# dynalo_SMD_MOD.net
KiCad netlist of a schematic drawn in EAGLE
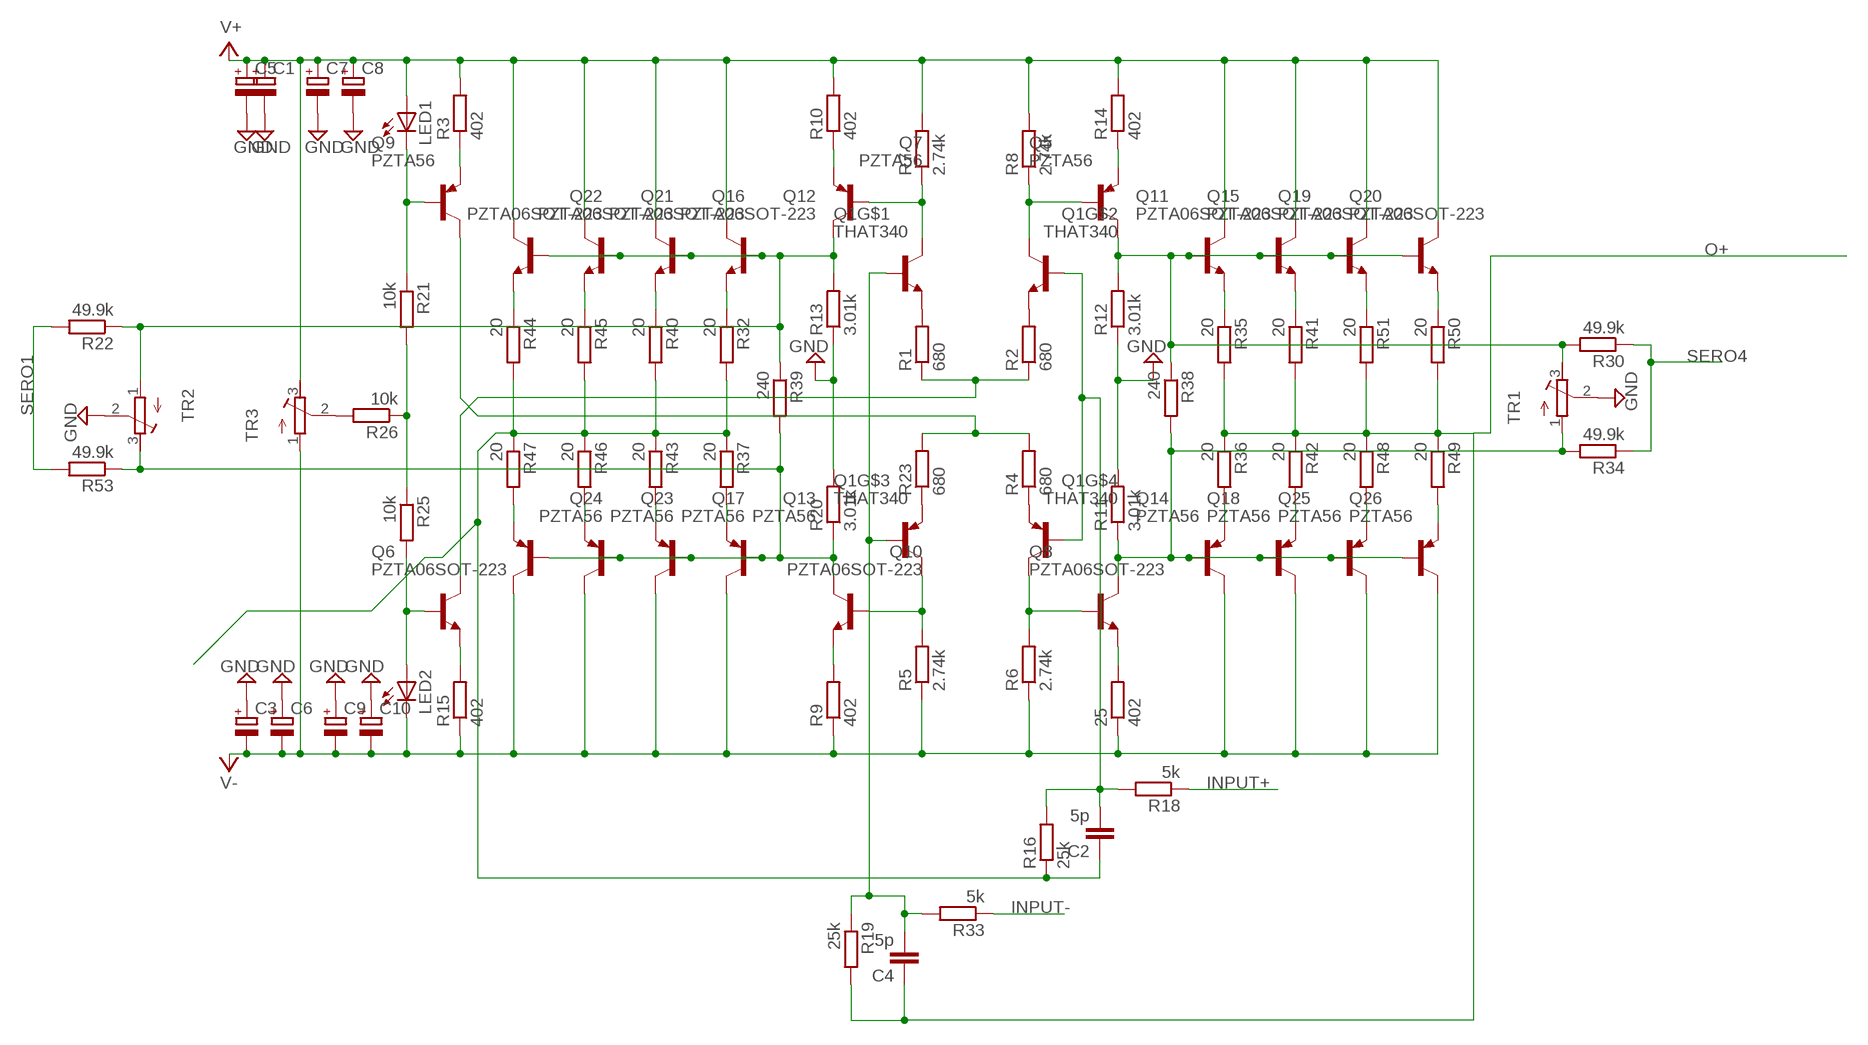
[diagram p0: schematic, sheet 1]

(export (version "E")
  (design (tool "Eeschema 10.0.6"))
  (components
    (comp (ref "25")
      (value "402")
      (footprint "eagle-import:MINI_MELF-0204W")
      (libsource (lib "eagle-import") (part "R-EU_MELF0204W"))
    )
    (comp (ref "C1")
      (value "CPOL-EUSP-CAP-CX")
      (footprint "eagle-import:SP-CAP-CX")
      (libsource (lib "eagle-import") (part "CPOL-EUSP-CAP-CX"))
    )
    (comp (ref "C2")
      (value "5p")
      (footprint "eagle-import:C0805")
      (libsource (lib "eagle-import") (part "C-EUC0805"))
    )
    (comp (ref "C3")
      (value "CPOL-EUSP-CAP-CX")
      (footprint "eagle-import:SP-CAP-CX")
      (libsource (lib "eagle-import") (part "CPOL-EUSP-CAP-CX"))
    )
    (comp (ref "C4")
      (value "5p")
      (footprint "eagle-import:C0805")
      (libsource (lib "eagle-import") (part "C-EUC0805"))
    )
    (comp (ref "C5")
      (value "CPOL-EUSP-CAP-CX")
      (footprint "eagle-import:SP-CAP-CX")
      (libsource (lib "eagle-import") (part "CPOL-EUSP-CAP-CX"))
    )
    (comp (ref "C6")
      (value "CPOL-EUSP-CAP-CX")
      (footprint "eagle-import:SP-CAP-CX")
      (libsource (lib "eagle-import") (part "CPOL-EUSP-CAP-CX"))
    )
    (comp (ref "C7")
      (value "CPOL-EUSP-CAP-CX")
      (footprint "eagle-import:SP-CAP-CX")
      (libsource (lib "eagle-import") (part "CPOL-EUSP-CAP-CX"))
    )
    (comp (ref "C8")
      (value "CPOL-EUSP-CAP-CX")
      (footprint "eagle-import:SP-CAP-CX")
      (libsource (lib "eagle-import") (part "CPOL-EUSP-CAP-CX"))
    )
    (comp (ref "C9")
      (value "CPOL-EUSP-CAP-CX")
      (footprint "eagle-import:SP-CAP-CX")
      (libsource (lib "eagle-import") (part "CPOL-EUSP-CAP-CX"))
    )
    (comp (ref "C10")
      (value "CPOL-EUSP-CAP-CX")
      (footprint "eagle-import:SP-CAP-CX")
      (libsource (lib "eagle-import") (part "CPOL-EUSP-CAP-CX"))
    )
    (comp (ref "LED1")
      (value "LED5MM")
      (footprint "eagle-import:LED5MM")
      (libsource (lib "eagle-import") (part "LED5MM"))
    )
    (comp (ref "LED2")
      (value "LED5MM")
      (footprint "eagle-import:LED5MM")
      (libsource (lib "eagle-import") (part "LED5MM"))
    )
    (comp (ref "Q1")
      (value "THAT340")
      (footprint "eagle-import:DIP254P762X510-14")
      (libsource (lib "eagle-import") (part "THAT340"))
    )
    (comp (ref "Q5")
      (value "PZTA56")
      (footprint "eagle-import:SOT223")
      (libsource (lib "eagle-import") (part "PZTA56"))
    )
    (comp (ref "Q6")
      (value "PZTA06SOT-223")
      (footprint "eagle-import:SOT223")
      (libsource (lib "eagle-import") (part "PZTA06SOT-223"))
    )
    (comp (ref "Q7")
      (value "PZTA56")
      (footprint "eagle-import:SOT223")
      (libsource (lib "eagle-import") (part "PZTA56"))
    )
    (comp (ref "Q8")
      (value "PZTA06SOT-223")
      (footprint "eagle-import:SOT223")
      (libsource (lib "eagle-import") (part "PZTA06SOT-223"))
    )
    (comp (ref "Q9")
      (value "PZTA56")
      (footprint "eagle-import:SOT223")
      (libsource (lib "eagle-import") (part "PZTA56"))
    )
    (comp (ref "Q10")
      (value "PZTA06SOT-223")
      (footprint "eagle-import:SOT223")
      (libsource (lib "eagle-import") (part "PZTA06SOT-223"))
    )
    (comp (ref "Q11")
      (value "PZTA06SOT-223")
      (footprint "eagle-import:SOT223")
      (libsource (lib "eagle-import") (part "PZTA06SOT-223"))
    )
    (comp (ref "Q12")
      (value "PZTA06SOT-223")
      (footprint "eagle-import:SOT223")
      (libsource (lib "eagle-import") (part "PZTA06SOT-223"))
    )
    (comp (ref "Q13")
      (value "PZTA56")
      (footprint "eagle-import:SOT223")
      (libsource (lib "eagle-import") (part "PZTA56"))
    )
    (comp (ref "Q14")
      (value "PZTA56")
      (footprint "eagle-import:SOT223")
      (libsource (lib "eagle-import") (part "PZTA56"))
    )
    (comp (ref "Q15")
      (value "PZTA06SOT-223")
      (footprint "eagle-import:SOT223")
      (libsource (lib "eagle-import") (part "PZTA06SOT-223"))
    )
    (comp (ref "Q16")
      (value "PZTA06SOT-223")
      (footprint "eagle-import:SOT223")
      (libsource (lib "eagle-import") (part "PZTA06SOT-223"))
    )
    (comp (ref "Q17")
      (value "PZTA56")
      (footprint "eagle-import:SOT223")
      (libsource (lib "eagle-import") (part "PZTA56"))
    )
    (comp (ref "Q18")
      (value "PZTA56")
      (footprint "eagle-import:SOT223")
      (libsource (lib "eagle-import") (part "PZTA56"))
    )
    (comp (ref "Q19")
      (value "PZTA06SOT-223")
      (footprint "eagle-import:SOT223")
      (libsource (lib "eagle-import") (part "PZTA06SOT-223"))
    )
    (comp (ref "Q20")
      (value "PZTA06SOT-223")
      (footprint "eagle-import:SOT223")
      (libsource (lib "eagle-import") (part "PZTA06SOT-223"))
    )
    (comp (ref "Q21")
      (value "PZTA06SOT-223")
      (footprint "eagle-import:SOT223")
      (libsource (lib "eagle-import") (part "PZTA06SOT-223"))
    )
    (comp (ref "Q22")
      (value "PZTA06SOT-223")
      (footprint "eagle-import:SOT223")
      (libsource (lib "eagle-import") (part "PZTA06SOT-223"))
    )
    (comp (ref "Q23")
      (value "PZTA56")
      (footprint "eagle-import:SOT223")
      (libsource (lib "eagle-import") (part "PZTA56"))
    )
    (comp (ref "Q24")
      (value "PZTA56")
      (footprint "eagle-import:SOT223")
      (libsource (lib "eagle-import") (part "PZTA56"))
    )
    (comp (ref "Q25")
      (value "PZTA56")
      (footprint "eagle-import:SOT223")
      (libsource (lib "eagle-import") (part "PZTA56"))
    )
    (comp (ref "Q26")
      (value "PZTA56")
      (footprint "eagle-import:SOT223")
      (libsource (lib "eagle-import") (part "PZTA56"))
    )
    (comp (ref "R1")
      (value "680")
      (footprint "eagle-import:MINI_MELF-0204W")
      (libsource (lib "eagle-import") (part "R-EU_MELF0204W"))
    )
    (comp (ref "R2")
      (value "680")
      (footprint "eagle-import:MINI_MELF-0204W")
      (libsource (lib "eagle-import") (part "R-EU_MELF0204W"))
    )
    (comp (ref "R3")
      (value "402")
      (footprint "eagle-import:MINI_MELF-0204W")
      (libsource (lib "eagle-import") (part "R-EU_MELF0204W"))
    )
    (comp (ref "R4")
      (value "680")
      (footprint "eagle-import:MINI_MELF-0204W")
      (libsource (lib "eagle-import") (part "R-EU_MELF0204W"))
    )
    (comp (ref "R5")
      (value "2.74k")
      (footprint "eagle-import:MINI_MELF-0204W")
      (libsource (lib "eagle-import") (part "R-EU_MELF0204W"))
    )
    (comp (ref "R6")
      (value "2.74k")
      (footprint "eagle-import:MINI_MELF-0204W")
      (libsource (lib "eagle-import") (part "R-EU_MELF0204W"))
    )
    (comp (ref "R7")
      (value "2.74k")
      (footprint "eagle-import:MINI_MELF-0204W")
      (libsource (lib "eagle-import") (part "R-EU_MELF0204W"))
    )
    (comp (ref "R8")
      (value "2.74k")
      (footprint "eagle-import:MINI_MELF-0204W")
      (libsource (lib "eagle-import") (part "R-EU_MELF0204W"))
    )
    (comp (ref "R9")
      (value "402")
      (footprint "eagle-import:MINI_MELF-0204W")
      (libsource (lib "eagle-import") (part "R-EU_MELF0204W"))
    )
    (comp (ref "R10")
      (value "402")
      (footprint "eagle-import:MINI_MELF-0204W")
      (libsource (lib "eagle-import") (part "R-EU_MELF0204W"))
    )
    (comp (ref "R11")
      (value "3.01k")
      (footprint "eagle-import:MINI_MELF-0204W")
      (libsource (lib "eagle-import") (part "R-EU_MELF0204W"))
    )
    (comp (ref "R12")
      (value "3.01k")
      (footprint "eagle-import:MINI_MELF-0204W")
      (libsource (lib "eagle-import") (part "R-EU_MELF0204W"))
    )
    (comp (ref "R13")
      (value "3.01k")
      (footprint "eagle-import:MINI_MELF-0204W")
      (libsource (lib "eagle-import") (part "R-EU_MELF0204W"))
    )
    (comp (ref "R14")
      (value "402")
      (footprint "eagle-import:MINI_MELF-0204W")
      (libsource (lib "eagle-import") (part "R-EU_MELF0204W"))
    )
    (comp (ref "R15")
      (value "402")
      (footprint "eagle-import:MINI_MELF-0204W")
      (libsource (lib "eagle-import") (part "R-EU_MELF0204W"))
    )
    (comp (ref "R16")
      (value "25k")
      (footprint "eagle-import:MINI_MELF-0204W")
      (libsource (lib "eagle-import") (part "R-EU_MELF0204W"))
    )
    (comp (ref "R18")
      (value "5k")
      (footprint "eagle-import:MINI_MELF-0204W")
      (libsource (lib "eagle-import") (part "R-EU_MELF0204W"))
    )
    (comp (ref "R19")
      (value "25k")
      (footprint "eagle-import:MINI_MELF-0204W")
      (libsource (lib "eagle-import") (part "R-EU_MELF0204W"))
    )
    (comp (ref "R20")
      (value "3.01k")
      (footprint "eagle-import:MINI_MELF-0204W")
      (libsource (lib "eagle-import") (part "R-EU_MELF0204W"))
    )
    (comp (ref "R21")
      (value "10k")
      (footprint "eagle-import:MINI_MELF-0204W")
      (libsource (lib "eagle-import") (part "R-EU_MELF0204W"))
    )
    (comp (ref "R22")
      (value "49.9k")
      (footprint "eagle-import:MINI_MELF-0204W")
      (libsource (lib "eagle-import") (part "R-EU_MELF0204W"))
    )
    (comp (ref "R23")
      (value "680")
      (footprint "eagle-import:MINI_MELF-0204W")
      (libsource (lib "eagle-import") (part "R-EU_MELF0204W"))
    )
    (comp (ref "R25")
      (value "10k")
      (footprint "eagle-import:MINI_MELF-0204W")
      (libsource (lib "eagle-import") (part "R-EU_MELF0204W"))
    )
    (comp (ref "R26")
      (value "10k")
      (footprint "eagle-import:MINI_MELF-0204W")
      (libsource (lib "eagle-import") (part "R-EU_MELF0204W"))
    )
    (comp (ref "R30")
      (value "49.9k")
      (footprint "eagle-import:MINI_MELF-0204W")
      (libsource (lib "eagle-import") (part "R-EU_MELF0204W"))
    )
    (comp (ref "R32")
      (value "20")
      (footprint "eagle-import:MINI_MELF-0204W")
      (libsource (lib "eagle-import") (part "R-EU_MELF0204W"))
    )
    (comp (ref "R33")
      (value "5k")
      (footprint "eagle-import:MINI_MELF-0204W")
      (libsource (lib "eagle-import") (part "R-EU_MELF0204W"))
    )
    (comp (ref "R34")
      (value "49.9k")
      (footprint "eagle-import:MINI_MELF-0204W")
      (libsource (lib "eagle-import") (part "R-EU_MELF0204W"))
    )
    (comp (ref "R35")
      (value "20")
      (footprint "eagle-import:MINI_MELF-0204W")
      (libsource (lib "eagle-import") (part "R-EU_MELF0204W"))
    )
    (comp (ref "R36")
      (value "20")
      (footprint "eagle-import:MINI_MELF-0204W")
      (libsource (lib "eagle-import") (part "R-EU_MELF0204W"))
    )
    (comp (ref "R37")
      (value "20")
      (footprint "eagle-import:MINI_MELF-0204W")
      (libsource (lib "eagle-import") (part "R-EU_MELF0204W"))
    )
    (comp (ref "R38")
      (value "240")
      (footprint "eagle-import:MINI_MELF-0204W")
      (libsource (lib "eagle-import") (part "R-EU_MELF0204W"))
    )
    (comp (ref "R39")
      (value "240")
      (footprint "eagle-import:MINI_MELF-0204W")
      (libsource (lib "eagle-import") (part "R-EU_MELF0204W"))
    )
    (comp (ref "R40")
      (value "20")
      (footprint "eagle-import:MINI_MELF-0204W")
      (libsource (lib "eagle-import") (part "R-EU_MELF0204W"))
    )
    (comp (ref "R41")
      (value "20")
      (footprint "eagle-import:MINI_MELF-0204W")
      (libsource (lib "eagle-import") (part "R-EU_MELF0204W"))
    )
    (comp (ref "R42")
      (value "20")
      (footprint "eagle-import:MINI_MELF-0204W")
      (libsource (lib "eagle-import") (part "R-EU_MELF0204W"))
    )
    (comp (ref "R43")
      (value "20")
      (footprint "eagle-import:MINI_MELF-0204W")
      (libsource (lib "eagle-import") (part "R-EU_MELF0204W"))
    )
    (comp (ref "R44")
      (value "20")
      (footprint "eagle-import:MINI_MELF-0204W")
      (libsource (lib "eagle-import") (part "R-EU_MELF0204W"))
    )
    (comp (ref "R45")
      (value "20")
      (footprint "eagle-import:MINI_MELF-0204W")
      (libsource (lib "eagle-import") (part "R-EU_MELF0204W"))
    )
    (comp (ref "R46")
      (value "20")
      (footprint "eagle-import:MINI_MELF-0204W")
      (libsource (lib "eagle-import") (part "R-EU_MELF0204W"))
    )
    (comp (ref "R47")
      (value "20")
      (footprint "eagle-import:MINI_MELF-0204W")
      (libsource (lib "eagle-import") (part "R-EU_MELF0204W"))
    )
    (comp (ref "R48")
      (value "20")
      (footprint "eagle-import:MINI_MELF-0204W")
      (libsource (lib "eagle-import") (part "R-EU_MELF0204W"))
    )
    (comp (ref "R49")
      (value "20")
      (footprint "eagle-import:MINI_MELF-0204W")
      (libsource (lib "eagle-import") (part "R-EU_MELF0204W"))
    )
    (comp (ref "R50")
      (value "20")
      (footprint "eagle-import:MINI_MELF-0204W")
      (libsource (lib "eagle-import") (part "R-EU_MELF0204W"))
    )
    (comp (ref "R51")
      (value "20")
      (footprint "eagle-import:MINI_MELF-0204W")
      (libsource (lib "eagle-import") (part "R-EU_MELF0204W"))
    )
    (comp (ref "R53")
      (value "49.9k")
      (footprint "eagle-import:MINI_MELF-0204W")
      (libsource (lib "eagle-import") (part "R-EU_MELF0204W"))
    )
    (comp (ref "TR1")
      (value "R-TRIMM3296W")
      (footprint "eagle-import:RTRIM3296W")
      (libsource (lib "eagle-import") (part "R-TRIMM3296W"))
    )
    (comp (ref "TR2")
      (value "R-TRIMM3296W")
      (footprint "eagle-import:RTRIM3296W")
      (libsource (lib "eagle-import") (part "R-TRIMM3296W"))
    )
    (comp (ref "TR3")
      (value "R-TRIMM3296W")
      (footprint "eagle-import:RTRIM3296W")
      (libsource (lib "eagle-import") (part "R-TRIMM3296W"))
    )
  )
  (nets
    (net (code "1") (name "/INPUT+") (class "Default")
      (node (ref "R18") (pin "1") (pinfunction "1_1") (pintype "passive"))
    )
    (net (code "2") (name "/INPUT-") (class "Default")
      (node (ref "R33") (pin "1") (pinfunction "1_1") (pintype "passive"))
    )
    (net (code "3") (name "/O+") (class "Default")
      (node (ref "C4") (pin "1") (pinfunction "1_1") (pintype "passive"))
      (node (ref "R19") (pin "2") (pinfunction "2_2") (pintype "passive"))
      (node (ref "R35") (pin "2") (pinfunction "2_2") (pintype "passive"))
      (node (ref "R36") (pin "1") (pinfunction "1_1") (pintype "passive"))
      (node (ref "R41") (pin "2") (pinfunction "2_2") (pintype "passive"))
      (node (ref "R42") (pin "1") (pinfunction "1_1") (pintype "passive"))
      (node (ref "R48") (pin "1") (pinfunction "1_1") (pintype "passive"))
      (node (ref "R49") (pin "1") (pinfunction "1_1") (pintype "passive"))
      (node (ref "R50") (pin "2") (pinfunction "2_2") (pintype "passive"))
      (node (ref "R51") (pin "2") (pinfunction "2_2") (pintype "passive"))
    )
    (net (code "4") (name "/SERO1") (class "Default")
      (node (ref "R22") (pin "2") (pinfunction "2_2") (pintype "passive"))
      (node (ref "R53") (pin "2") (pinfunction "2_2") (pintype "passive"))
    )
    (net (code "5") (name "/SERO4") (class "Default")
      (node (ref "R30") (pin "1") (pinfunction "1_1") (pintype "passive"))
      (node (ref "R34") (pin "1") (pinfunction "1_1") (pintype "passive"))
    )
    (net (code "6") (name "GND") (class "Default")
      (node (ref "C1") (pin "-") (pinfunction "-_-") (pintype "passive"))
      (node (ref "C10") (pin "+") (pinfunction "+_+") (pintype "passive"))
      (node (ref "C3") (pin "+") (pinfunction "+_+") (pintype "passive"))
      (node (ref "C5") (pin "-") (pinfunction "-_-") (pintype "passive"))
      (node (ref "C6") (pin "+") (pinfunction "+_+") (pintype "passive"))
      (node (ref "C7") (pin "-") (pinfunction "-_-") (pintype "passive"))
      (node (ref "C8") (pin "-") (pinfunction "-_-") (pintype "passive"))
      (node (ref "C9") (pin "+") (pinfunction "+_+") (pintype "passive"))
      (node (ref "R11") (pin "2") (pinfunction "2_2") (pintype "passive"))
      (node (ref "R12") (pin "1") (pinfunction "1_1") (pintype "passive"))
      (node (ref "R13") (pin "1") (pinfunction "1_1") (pintype "passive"))
      (node (ref "R20") (pin "2") (pinfunction "2_2") (pintype "passive"))
      (node (ref "TR1") (pin "2") (pinfunction "S_2") (pintype "passive"))
      (node (ref "TR2") (pin "2") (pinfunction "S_2") (pintype "passive"))
    )
    (net (code "7") (name "Net-(C2-Pad1)") (class "Default")
      (node (ref "C2") (pin "1") (pinfunction "1_1") (pintype "passive"))
      (node (ref "R16") (pin "1") (pinfunction "1_1") (pintype "passive"))
      (node (ref "R32") (pin "2") (pinfunction "2_2") (pintype "passive"))
      (node (ref "R37") (pin "1") (pinfunction "1_1") (pintype "passive"))
      (node (ref "R40") (pin "2") (pinfunction "2_2") (pintype "passive"))
      (node (ref "R43") (pin "1") (pinfunction "1_1") (pintype "passive"))
      (node (ref "R44") (pin "2") (pinfunction "2_2") (pintype "passive"))
      (node (ref "R45") (pin "2") (pinfunction "2_2") (pintype "passive"))
      (node (ref "R46") (pin "1") (pinfunction "1_1") (pintype "passive"))
      (node (ref "R47") (pin "1") (pinfunction "1_1") (pintype "passive"))
    )
    (net (code "8") (name "Net-(LED1-C)") (class "Default")
      (node (ref "LED1") (pin "K") (pinfunction "C_K") (pintype "passive"))
      (node (ref "Q9") (pin "1") (pinfunction "B_1") (pintype "passive"))
      (node (ref "R21") (pin "1") (pinfunction "1_1") (pintype "passive"))
    )
    (net (code "9") (name "Net-(Q1A-B)") (class "Default")
      (node (ref "C4") (pin "2") (pinfunction "2_2") (pintype "passive"))
      (node (ref "Q1") (pin "2") (pinfunction "B_2") (pintype "passive"))
      (node (ref "Q1") (pin "6") (pinfunction "B_6") (pintype "passive"))
      (node (ref "R19") (pin "1") (pinfunction "1_1") (pintype "passive"))
      (node (ref "R33") (pin "2") (pinfunction "2_2") (pintype "passive"))
    )
    (net (code "10") (name "Net-(Q1A-C)") (class "Default")
      (node (ref "Q1") (pin "1") (pinfunction "C_1") (pintype "passive"))
      (node (ref "Q7") (pin "1") (pinfunction "B_1") (pintype "passive"))
      (node (ref "R7") (pin "1") (pinfunction "1_1") (pintype "passive"))
    )
    (net (code "11") (name "Net-(Q1A-E)") (class "Default")
      (node (ref "Q1") (pin "3") (pinfunction "E_3") (pintype "passive"))
      (node (ref "R1") (pin "2") (pinfunction "2_2") (pintype "passive"))
    )
    (net (code "12") (name "Net-(Q1B-B)") (class "Default")
      (node (ref "C2") (pin "2") (pinfunction "2_2") (pintype "passive"))
      (node (ref "Q1") (pin "13") (pinfunction "B_13") (pintype "passive"))
      (node (ref "Q1") (pin "9") (pinfunction "B_9") (pintype "passive"))
      (node (ref "R16") (pin "2") (pinfunction "2_2") (pintype "passive"))
      (node (ref "R18") (pin "2") (pinfunction "2_2") (pintype "passive"))
    )
    (net (code "13") (name "Net-(Q1B-C)") (class "Default")
      (node (ref "Q1") (pin "14") (pinfunction "C_14") (pintype "passive"))
      (node (ref "Q5") (pin "1") (pinfunction "B_1") (pintype "passive"))
      (node (ref "R8") (pin "1") (pinfunction "1_1") (pintype "passive"))
    )
    (net (code "14") (name "Net-(Q1B-E)") (class "Default")
      (node (ref "Q1") (pin "12") (pinfunction "E_12") (pintype "passive"))
      (node (ref "R2") (pin "2") (pinfunction "2_2") (pintype "passive"))
    )
    (net (code "15") (name "Net-(Q1C-E)") (class "Default")
      (node (ref "Q1") (pin "5") (pinfunction "E_5") (pintype "passive"))
      (node (ref "R23") (pin "1") (pinfunction "1_1") (pintype "passive"))
    )
    (net (code "16") (name "Net-(Q1D-C)") (class "Default")
      (node (ref "Q1") (pin "8") (pinfunction "C_8") (pintype "passive"))
      (node (ref "Q8") (pin "1") (pinfunction "B_1") (pintype "passive"))
      (node (ref "R6") (pin "2") (pinfunction "2_2") (pintype "passive"))
    )
    (net (code "17") (name "Net-(Q1D-E)") (class "Default")
      (node (ref "Q1") (pin "10") (pinfunction "E_10") (pintype "passive"))
      (node (ref "R4") (pin "1") (pinfunction "1_1") (pintype "passive"))
    )
    (net (code "18") (name "Net-(Q5-E)") (class "Default")
      (node (ref "Q5") (pin "3") (pinfunction "E_3") (pintype "passive"))
      (node (ref "R14") (pin "1") (pinfunction "1_1") (pintype "passive"))
    )
    (net (code "19") (name "Net-(Q6-B)") (class "Default")
      (node (ref "LED2") (pin "A") (pinfunction "A_A") (pintype "passive"))
      (node (ref "Q6") (pin "1") (pinfunction "B_1") (pintype "passive"))
      (node (ref "R25") (pin "2") (pinfunction "2_2") (pintype "passive"))
    )
    (net (code "20") (name "Net-(Q6-C-Pad2)") (class "Default")
      (node (ref "Q6") (pin "2") (pinfunction "C_2") (pintype "passive"))
      (node (ref "Q6") (pin "4") (pinfunction "C_4") (pintype "passive"))
      (node (ref "R1") (pin "1") (pinfunction "1_1") (pintype "passive"))
      (node (ref "R2") (pin "1") (pinfunction "1_1") (pintype "passive"))
    )
    (net (code "21") (name "Net-(Q6-E)") (class "Default")
      (node (ref "Q6") (pin "3") (pinfunction "E_3") (pintype "passive"))
      (node (ref "R15") (pin "2") (pinfunction "2_2") (pintype "passive"))
    )
    (net (code "22") (name "Net-(Q7-E)") (class "Default")
      (node (ref "Q7") (pin "3") (pinfunction "E_3") (pintype "passive"))
      (node (ref "R10") (pin "1") (pinfunction "1_1") (pintype "passive"))
    )
    (net (code "23") (name "Net-(Q8-E)") (class "Default")
      (node (ref "25") (pin "2") (pinfunction "2_2") (pintype "passive"))
      (node (ref "Q8") (pin "3") (pinfunction "E_3") (pintype "passive"))
    )
    (net (code "24") (name "Net-(Q9-C-Pad2)") (class "Default")
      (node (ref "Q9") (pin "2") (pinfunction "C_2") (pintype "passive"))
      (node (ref "Q9") (pin "4") (pinfunction "C_4") (pintype "passive"))
      (node (ref "R23") (pin "2") (pinfunction "2_2") (pintype "passive"))
      (node (ref "R4") (pin "2") (pinfunction "2_2") (pintype "passive"))
    )
    (net (code "25") (name "Net-(Q9-E)") (class "Default")
      (node (ref "Q9") (pin "3") (pinfunction "E_3") (pintype "passive"))
      (node (ref "R3") (pin "1") (pinfunction "1_1") (pintype "passive"))
    )
    (net (code "26") (name "Net-(Q10-B)") (class "Default")
      (node (ref "Q1") (pin "7") (pinfunction "C_7") (pintype "passive"))
      (node (ref "Q10") (pin "1") (pinfunction "B_1") (pintype "passive"))
      (node (ref "R5") (pin "2") (pinfunction "2_2") (pintype "passive"))
    )
    (net (code "27") (name "Net-(Q10-E)") (class "Default")
      (node (ref "Q10") (pin "3") (pinfunction "E_3") (pintype "passive"))
      (node (ref "R9") (pin "2") (pinfunction "2_2") (pintype "passive"))
    )
    (net (code "28") (name "Net-(Q11-B)") (class "Default")
      (node (ref "Q11") (pin "1") (pinfunction "B_1") (pintype "passive"))
      (node (ref "Q15") (pin "1") (pinfunction "B_1") (pintype "passive"))
      (node (ref "Q19") (pin "1") (pinfunction "B_1") (pintype "passive"))
      (node (ref "Q20") (pin "1") (pinfunction "B_1") (pintype "passive"))
      (node (ref "Q5") (pin "2") (pinfunction "C_2") (pintype "passive"))
      (node (ref "Q5") (pin "4") (pinfunction "C_4") (pintype "passive"))
      (node (ref "R12") (pin "2") (pinfunction "2_2") (pintype "passive"))
      (node (ref "R30") (pin "2") (pinfunction "2_2") (pintype "passive"))
      (node (ref "R38") (pin "1") (pinfunction "1_1") (pintype "passive"))
      (node (ref "TR1") (pin "3") (pinfunction "E_3") (pintype "passive"))
    )
    (net (code "29") (name "Net-(Q11-E)") (class "Default")
      (node (ref "Q11") (pin "3") (pinfunction "E_3") (pintype "passive"))
      (node (ref "R35") (pin "1") (pinfunction "1_1") (pintype "passive"))
    )
    (net (code "30") (name "Net-(Q12-B)") (class "Default")
      (node (ref "Q12") (pin "1") (pinfunction "B_1") (pintype "passive"))
      (node (ref "Q16") (pin "1") (pinfunction "B_1") (pintype "passive"))
      (node (ref "Q21") (pin "1") (pinfunction "B_1") (pintype "passive"))
      (node (ref "Q22") (pin "1") (pinfunction "B_1") (pintype "passive"))
      (node (ref "Q7") (pin "2") (pinfunction "C_2") (pintype "passive"))
      (node (ref "Q7") (pin "4") (pinfunction "C_4") (pintype "passive"))
      (node (ref "R13") (pin "2") (pinfunction "2_2") (pintype "passive"))
      (node (ref "R22") (pin "1") (pinfunction "1_1") (pintype "passive"))
      (node (ref "R39") (pin "1") (pinfunction "1_1") (pintype "passive"))
      (node (ref "TR2") (pin "1") (pinfunction "A_1") (pintype "passive"))
    )
    (net (code "31") (name "Net-(Q12-E)") (class "Default")
      (node (ref "Q12") (pin "3") (pinfunction "E_3") (pintype "passive"))
      (node (ref "R32") (pin "1") (pinfunction "1_1") (pintype "passive"))
    )
    (net (code "32") (name "Net-(Q13-B)") (class "Default")
      (node (ref "Q10") (pin "2") (pinfunction "C_2") (pintype "passive"))
      (node (ref "Q10") (pin "4") (pinfunction "C_4") (pintype "passive"))
      (node (ref "Q13") (pin "1") (pinfunction "B_1") (pintype "passive"))
      (node (ref "Q17") (pin "1") (pinfunction "B_1") (pintype "passive"))
      (node (ref "Q23") (pin "1") (pinfunction "B_1") (pintype "passive"))
      (node (ref "Q24") (pin "1") (pinfunction "B_1") (pintype "passive"))
      (node (ref "R20") (pin "1") (pinfunction "1_1") (pintype "passive"))
      (node (ref "R39") (pin "2") (pinfunction "2_2") (pintype "passive"))
      (node (ref "R53") (pin "1") (pinfunction "1_1") (pintype "passive"))
      (node (ref "TR2") (pin "3") (pinfunction "E_3") (pintype "passive"))
    )
    (net (code "33") (name "Net-(Q13-E)") (class "Default")
      (node (ref "Q13") (pin "3") (pinfunction "E_3") (pintype "passive"))
      (node (ref "R37") (pin "2") (pinfunction "2_2") (pintype "passive"))
    )
    (net (code "34") (name "Net-(Q14-B)") (class "Default")
      (node (ref "Q14") (pin "1") (pinfunction "B_1") (pintype "passive"))
      (node (ref "Q18") (pin "1") (pinfunction "B_1") (pintype "passive"))
      (node (ref "Q25") (pin "1") (pinfunction "B_1") (pintype "passive"))
      (node (ref "Q26") (pin "1") (pinfunction "B_1") (pintype "passive"))
      (node (ref "Q8") (pin "2") (pinfunction "C_2") (pintype "passive"))
      (node (ref "Q8") (pin "4") (pinfunction "C_4") (pintype "passive"))
      (node (ref "R11") (pin "1") (pinfunction "1_1") (pintype "passive"))
      (node (ref "R34") (pin "2") (pinfunction "2_2") (pintype "passive"))
      (node (ref "R38") (pin "2") (pinfunction "2_2") (pintype "passive"))
      (node (ref "TR1") (pin "1") (pinfunction "A_1") (pintype "passive"))
    )
    (net (code "35") (name "Net-(Q14-E)") (class "Default")
      (node (ref "Q14") (pin "3") (pinfunction "E_3") (pintype "passive"))
      (node (ref "R36") (pin "2") (pinfunction "2_2") (pintype "passive"))
    )
    (net (code "36") (name "Net-(Q15-E)") (class "Default")
      (node (ref "Q15") (pin "3") (pinfunction "E_3") (pintype "passive"))
      (node (ref "R41") (pin "1") (pinfunction "1_1") (pintype "passive"))
    )
    (net (code "37") (name "Net-(Q16-E)") (class "Default")
      (node (ref "Q16") (pin "3") (pinfunction "E_3") (pintype "passive"))
      (node (ref "R40") (pin "1") (pinfunction "1_1") (pintype "passive"))
    )
    (net (code "38") (name "Net-(Q17-E)") (class "Default")
      (node (ref "Q17") (pin "3") (pinfunction "E_3") (pintype "passive"))
      (node (ref "R43") (pin "2") (pinfunction "2_2") (pintype "passive"))
    )
    (net (code "39") (name "Net-(Q18-E)") (class "Default")
      (node (ref "Q18") (pin "3") (pinfunction "E_3") (pintype "passive"))
      (node (ref "R42") (pin "2") (pinfunction "2_2") (pintype "passive"))
    )
    (net (code "40") (name "Net-(Q19-E)") (class "Default")
      (node (ref "Q19") (pin "3") (pinfunction "E_3") (pintype "passive"))
      (node (ref "R51") (pin "1") (pinfunction "1_1") (pintype "passive"))
    )
    (net (code "41") (name "Net-(Q20-E)") (class "Default")
      (node (ref "Q20") (pin "3") (pinfunction "E_3") (pintype "passive"))
      (node (ref "R50") (pin "1") (pinfunction "1_1") (pintype "passive"))
    )
    (net (code "42") (name "Net-(Q21-E)") (class "Default")
      (node (ref "Q21") (pin "3") (pinfunction "E_3") (pintype "passive"))
      (node (ref "R45") (pin "1") (pinfunction "1_1") (pintype "passive"))
    )
    (net (code "43") (name "Net-(Q22-E)") (class "Default")
      (node (ref "Q22") (pin "3") (pinfunction "E_3") (pintype "passive"))
      (node (ref "R44") (pin "1") (pinfunction "1_1") (pintype "passive"))
    )
    (net (code "44") (name "Net-(Q23-E)") (class "Default")
      (node (ref "Q23") (pin "3") (pinfunction "E_3") (pintype "passive"))
      (node (ref "R46") (pin "2") (pinfunction "2_2") (pintype "passive"))
    )
    (net (code "45") (name "Net-(Q24-E)") (class "Default")
      (node (ref "Q24") (pin "3") (pinfunction "E_3") (pintype "passive"))
      (node (ref "R47") (pin "2") (pinfunction "2_2") (pintype "passive"))
    )
    (net (code "46") (name "Net-(Q25-E)") (class "Default")
      (node (ref "Q25") (pin "3") (pinfunction "E_3") (pintype "passive"))
      (node (ref "R48") (pin "2") (pinfunction "2_2") (pintype "passive"))
    )
    (net (code "47") (name "Net-(Q26-E)") (class "Default")
      (node (ref "Q26") (pin "3") (pinfunction "E_3") (pintype "passive"))
      (node (ref "R49") (pin "2") (pinfunction "2_2") (pintype "passive"))
    )
    (net (code "48") (name "Net-(R21-Pad2)") (class "Default")
      (node (ref "R21") (pin "2") (pinfunction "2_2") (pintype "passive"))
      (node (ref "R25") (pin "1") (pinfunction "1_1") (pintype "passive"))
      (node (ref "R26") (pin "1") (pinfunction "1_1") (pintype "passive"))
    )
    (net (code "49") (name "Net-(TR3-S)") (class "Default")
      (node (ref "R26") (pin "2") (pinfunction "2_2") (pintype "passive"))
      (node (ref "TR3") (pin "2") (pinfunction "S_2") (pintype "passive"))
    )
    (net (code "50") (name "V+") (class "Default")
      (node (ref "C1") (pin "+") (pinfunction "+_+") (pintype "passive"))
      (node (ref "C5") (pin "+") (pinfunction "+_+") (pintype "passive"))
      (node (ref "C7") (pin "+") (pinfunction "+_+") (pintype "passive"))
      (node (ref "C8") (pin "+") (pinfunction "+_+") (pintype "passive"))
      (node (ref "LED1") (pin "A") (pinfunction "A_A") (pintype "passive"))
      (node (ref "Q11") (pin "2") (pinfunction "C_2") (pintype "passive"))
      (node (ref "Q11") (pin "4") (pinfunction "C_4") (pintype "passive"))
      (node (ref "Q12") (pin "2") (pinfunction "C_2") (pintype "passive"))
      (node (ref "Q12") (pin "4") (pinfunction "C_4") (pintype "passive"))
      (node (ref "Q15") (pin "2") (pinfunction "C_2") (pintype "passive"))
      (node (ref "Q15") (pin "4") (pinfunction "C_4") (pintype "passive"))
      (node (ref "Q16") (pin "2") (pinfunction "C_2") (pintype "passive"))
      (node (ref "Q16") (pin "4") (pinfunction "C_4") (pintype "passive"))
      (node (ref "Q19") (pin "2") (pinfunction "C_2") (pintype "passive"))
      (node (ref "Q19") (pin "4") (pinfunction "C_4") (pintype "passive"))
      (node (ref "Q20") (pin "2") (pinfunction "C_2") (pintype "passive"))
      (node (ref "Q20") (pin "4") (pinfunction "C_4") (pintype "passive"))
      (node (ref "Q21") (pin "2") (pinfunction "C_2") (pintype "passive"))
      (node (ref "Q21") (pin "4") (pinfunction "C_4") (pintype "passive"))
      (node (ref "Q22") (pin "2") (pinfunction "C_2") (pintype "passive"))
      (node (ref "Q22") (pin "4") (pinfunction "C_4") (pintype "passive"))
      (node (ref "R10") (pin "2") (pinfunction "2_2") (pintype "passive"))
      (node (ref "R14") (pin "2") (pinfunction "2_2") (pintype "passive"))
      (node (ref "R3") (pin "2") (pinfunction "2_2") (pintype "passive"))
      (node (ref "R7") (pin "2") (pinfunction "2_2") (pintype "passive"))
      (node (ref "R8") (pin "2") (pinfunction "2_2") (pintype "passive"))
      (node (ref "TR3") (pin "3") (pinfunction "E_3") (pintype "passive"))
    )
    (net (code "51") (name "V-") (class "Default")
      (node (ref "25") (pin "1") (pinfunction "1_1") (pintype "passive"))
      (node (ref "C10") (pin "-") (pinfunction "-_-") (pintype "passive"))
      (node (ref "C3") (pin "-") (pinfunction "-_-") (pintype "passive"))
      (node (ref "C6") (pin "-") (pinfunction "-_-") (pintype "passive"))
      (node (ref "C9") (pin "-") (pinfunction "-_-") (pintype "passive"))
      (node (ref "LED2") (pin "K") (pinfunction "C_K") (pintype "passive"))
      (node (ref "Q13") (pin "2") (pinfunction "C_2") (pintype "passive"))
      (node (ref "Q13") (pin "4") (pinfunction "C_4") (pintype "passive"))
      (node (ref "Q14") (pin "2") (pinfunction "C_2") (pintype "passive"))
      (node (ref "Q14") (pin "4") (pinfunction "C_4") (pintype "passive"))
      (node (ref "Q17") (pin "2") (pinfunction "C_2") (pintype "passive"))
      (node (ref "Q17") (pin "4") (pinfunction "C_4") (pintype "passive"))
      (node (ref "Q18") (pin "2") (pinfunction "C_2") (pintype "passive"))
      (node (ref "Q18") (pin "4") (pinfunction "C_4") (pintype "passive"))
      (node (ref "Q23") (pin "2") (pinfunction "C_2") (pintype "passive"))
      (node (ref "Q23") (pin "4") (pinfunction "C_4") (pintype "passive"))
      (node (ref "Q24") (pin "2") (pinfunction "C_2") (pintype "passive"))
      (node (ref "Q24") (pin "4") (pinfunction "C_4") (pintype "passive"))
      (node (ref "Q25") (pin "2") (pinfunction "C_2") (pintype "passive"))
      (node (ref "Q25") (pin "4") (pinfunction "C_4") (pintype "passive"))
      (node (ref "Q26") (pin "2") (pinfunction "C_2") (pintype "passive"))
      (node (ref "Q26") (pin "4") (pinfunction "C_4") (pintype "passive"))
      (node (ref "R15") (pin "1") (pinfunction "1_1") (pintype "passive"))
      (node (ref "R5") (pin "1") (pinfunction "1_1") (pintype "passive"))
      (node (ref "R6") (pin "1") (pinfunction "1_1") (pintype "passive"))
      (node (ref "R9") (pin "1") (pinfunction "1_1") (pintype "passive"))
      (node (ref "TR3") (pin "1") (pinfunction "A_1") (pintype "passive"))
    )
  )
)
